# newMain.net
KiCad netlist of a schematic drawn in EAGLE
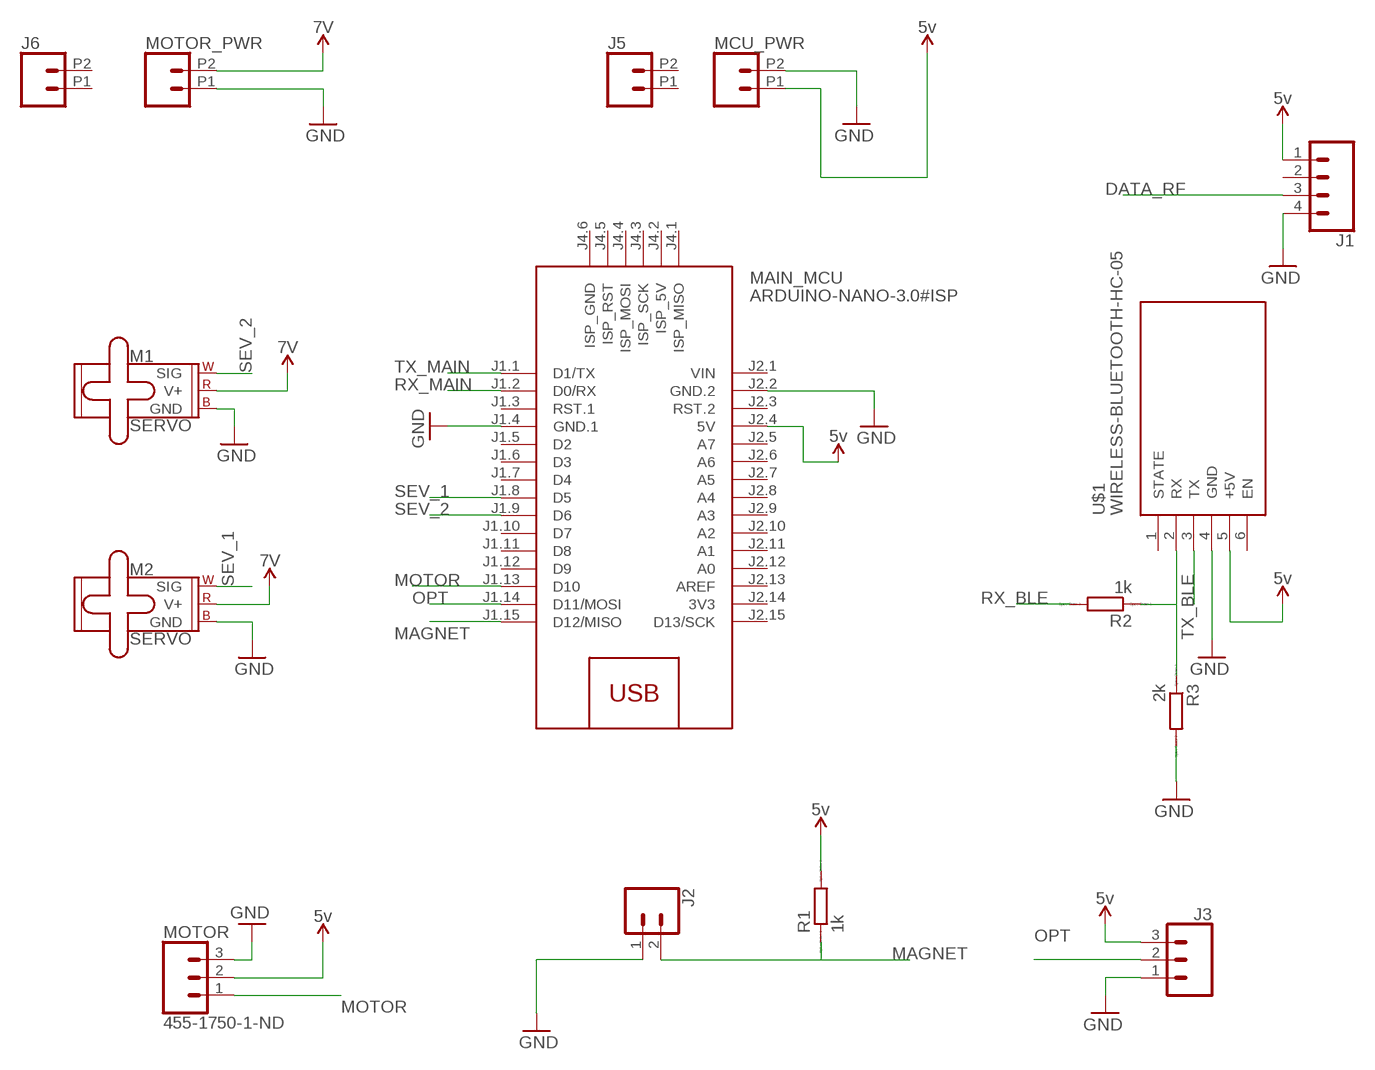
[diagram p0: schematic, sheet 1]

(export (version "E")
  (design (tool "Eeschema 10.0.6"))
  (components
    (comp (ref "J1")
      (value "CONN_04")
      (footprint "eagle-import:1X04")
      (libsource (lib "eagle-import") (part "CONN_04"))
    )
    (comp (ref "J2")
      (value "CONN_02")
      (footprint "eagle-import:1X02")
      (libsource (lib "eagle-import") (part "CONN_02"))
    )
    (comp (ref "J3")
      (value "CONN_03LOCK")
      (footprint "eagle-import:1X03_LOCK")
      (libsource (lib "eagle-import") (part "CONN_03LOCK"))
    )
    (comp (ref "J5")
      (value "CONN_022.54MM_SCREWTERM")
      (footprint "eagle-import:1X02_2.54_SCREWTERM")
      (libsource (lib "eagle-import") (part "SparkFun-Retired_CONN_022.54MM_SCREWTERM"))
    )
    (comp (ref "J6")
      (value "CONN_022.54MM_SCREWTERM")
      (footprint "eagle-import:1X02_2.54_SCREWTERM")
      (libsource (lib "eagle-import") (part "SparkFun-Retired_CONN_022.54MM_SCREWTERM"))
    )
    (comp (ref "M1")
      (value "SERVO")
      (footprint "eagle-import:1X03")
      (libsource (lib "eagle-import") (part "SERVO"))
    )
    (comp (ref "M2")
      (value "SERVO")
      (footprint "eagle-import:1X03")
      (libsource (lib "eagle-import") (part "SERVO"))
    )
    (comp (ref "MAIN_MCU")
      (value "ARDUINO-NANO-3.0#ISP")
      (footprint "eagle-import:ARDUINO-NANO-3.0#ISP")
      (libsource (lib "eagle-import") (part "ARDUINO-NANO-3.0#ISP"))
    )
    (comp (ref "MCU_PWR")
      (value "CONN_022.54MM_SCREWTERM")
      (footprint "eagle-import:1X02_2.54_SCREWTERM")
      (libsource (lib "eagle-import") (part "CONN_022.54MM_SCREWTERM"))
    )
    (comp (ref "MOTOR")
      (value "455-1750-1-ND")
      (footprint "eagle-import:1X03")
      (libsource (lib "eagle-import") (part "CONN_03"))
    )
    (comp (ref "MOTOR_PWR")
      (value "CONN_022.54MM_SCREWTERM")
      (footprint "eagle-import:1X02_2.54_SCREWTERM")
      (libsource (lib "eagle-import") (part "CONN_022.54MM_SCREWTERM"))
    )
    (comp (ref "R1")
      (value "1k")
      (footprint "eagle-import:0207_10")
      (libsource (lib "eagle-import") (part "R0207/10"))
    )
    (comp (ref "R2")
      (value "1k")
      (footprint "eagle-import:0207_10")
      (libsource (lib "eagle-import") (part "R0207/10"))
    )
    (comp (ref "R3")
      (value "2k")
      (footprint "eagle-import:0207_10")
      (libsource (lib "eagle-import") (part "R0207/10"))
    )
    (comp (ref "U$1")
      (value "WIRELESS-BLUETOOTH-HC-05")
      (footprint "eagle-import:WIRELESS-BLUETOOTH-HC-05")
      (libsource (lib "eagle-import") (part "WIRELESS-BLUETOOTH-HC-05"))
    )
  )
  (nets
    (net (code "1") (name "/3V3") (class "Default")
      (node (ref "MAIN_MCU") (pin "J2.14") (pinfunction "3V3_J2.14") (pintype "power_in"))
    )
    (net (code "2") (name "/DATA_RF") (class "Default")
      (node (ref "J1") (pin "3") (pinfunction "3_3") (pintype "passive"))
    )
    (net (code "3") (name "/MAGNET") (class "Default")
      (node (ref "J2") (pin "2") (pinfunction "2_2") (pintype "passive"))
      (node (ref "MAIN_MCU") (pin "J1.15") (pinfunction "D12/MISO_J1.15") (pintype "bidirectional"))
      (node (ref "R1") (pin "1") (pinfunction "1_1") (pintype "passive"))
    )
    (net (code "4") (name "/MOTOR") (class "Default")
      (node (ref "MAIN_MCU") (pin "J1.13") (pinfunction "D10_J1.13") (pintype "bidirectional"))
      (node (ref "MOTOR") (pin "1") (pinfunction "1_1") (pintype "passive"))
    )
    (net (code "5") (name "/OPT") (class "Default")
      (node (ref "J3") (pin "2") (pinfunction "2_2") (pintype "passive"))
      (node (ref "MAIN_MCU") (pin "J1.14") (pinfunction "D11/MOSI_J1.14") (pintype "bidirectional"))
    )
    (net (code "6") (name "/RX_BLE") (class "Default")
      (node (ref "R2") (pin "2") (pinfunction "2_2") (pintype "passive"))
    )
    (net (code "7") (name "/RX_MAIN") (class "Default")
      (node (ref "MAIN_MCU") (pin "J1.2") (pinfunction "D0/RX_J1.2") (pintype "bidirectional"))
    )
    (net (code "8") (name "/SEV_1") (class "Default")
      (node (ref "M2") (pin "1") (pinfunction "SIG_1") (pintype "bidirectional"))
      (node (ref "MAIN_MCU") (pin "J1.8") (pinfunction "D5_J1.8") (pintype "bidirectional"))
    )
    (net (code "9") (name "/SEV_2") (class "Default")
      (node (ref "M1") (pin "1") (pinfunction "SIG_1") (pintype "bidirectional"))
      (node (ref "MAIN_MCU") (pin "J1.9") (pinfunction "D6_J1.9") (pintype "bidirectional"))
    )
    (net (code "10") (name "/TX_BLE") (class "Default")
      (node (ref "U$1") (pin "3") (pinfunction "TX_3") (pintype "bidirectional"))
    )
    (net (code "11") (name "/TX_MAIN") (class "Default")
      (node (ref "MAIN_MCU") (pin "J1.1") (pinfunction "D1/TX_J1.1") (pintype "bidirectional"))
    )
    (net (code "12") (name "/VIN") (class "Default")
      (node (ref "MAIN_MCU") (pin "J2.1") (pinfunction "VIN_J2.1") (pintype "power_in"))
    )
    (net (code "13") (name "5v") (class "Default")
      (node (ref "J1") (pin "1") (pinfunction "1_1") (pintype "passive"))
      (node (ref "J3") (pin "3") (pinfunction "3_3") (pintype "passive"))
      (node (ref "MAIN_MCU") (pin "J2.4") (pinfunction "5V_J2.4") (pintype "power_in"))
      (node (ref "MCU_PWR") (pin "P1") (pinfunction "1_P1") (pintype "passive"))
      (node (ref "MOTOR") (pin "2") (pinfunction "2_2") (pintype "passive"))
      (node (ref "R1") (pin "2") (pinfunction "2_2") (pintype "passive"))
      (node (ref "U$1") (pin "5") (pinfunction "+5V_5") (pintype "power_in"))
    )
    (net (code "14") (name "7V") (class "Default")
      (node (ref "M1") (pin "2") (pinfunction "V+_2") (pintype "bidirectional"))
      (node (ref "M2") (pin "2") (pinfunction "V+_2") (pintype "bidirectional"))
      (node (ref "MOTOR_PWR") (pin "P2") (pinfunction "2_P2") (pintype "passive"))
    )
    (net (code "15") (name "GND") (class "Default")
      (node (ref "J1") (pin "4") (pinfunction "4_4") (pintype "passive"))
      (node (ref "J2") (pin "1") (pinfunction "1_1") (pintype "passive"))
      (node (ref "J3") (pin "1") (pinfunction "1_1") (pintype "passive"))
      (node (ref "M1") (pin "3") (pinfunction "GND_3") (pintype "bidirectional"))
      (node (ref "M2") (pin "3") (pinfunction "GND_3") (pintype "bidirectional"))
      (node (ref "MAIN_MCU") (pin "J1.4") (pinfunction "GND.1_J1.4") (pintype "power_in"))
      (node (ref "MAIN_MCU") (pin "J2.2") (pinfunction "GND.2_J2.2") (pintype "power_in"))
      (node (ref "MCU_PWR") (pin "P2") (pinfunction "2_P2") (pintype "passive"))
      (node (ref "MOTOR") (pin "3") (pinfunction "3_3") (pintype "passive"))
      (node (ref "MOTOR_PWR") (pin "P1") (pinfunction "1_P1") (pintype "passive"))
      (node (ref "R3") (pin "2") (pinfunction "2_2") (pintype "passive"))
      (node (ref "U$1") (pin "4") (pinfunction "GND_4") (pintype "power_in"))
    )
    (net (code "16") (name "Net-(U$1-RX)") (class "Default")
      (node (ref "R2") (pin "1") (pinfunction "1_1") (pintype "passive"))
      (node (ref "R3") (pin "1") (pinfunction "1_1") (pintype "passive"))
      (node (ref "U$1") (pin "2") (pinfunction "RX_2") (pintype "bidirectional"))
    )
    (net (code "17") (name "unconnected-(J1-Pad2)") (class "Default")
      (node (ref "J1") (pin "2") (pinfunction "2_2") (pintype "passive"))
    )
    (net (code "18") (name "unconnected-(J5-1-PadP1)") (class "Default")
      (node (ref "J5") (pin "P1") (pinfunction "1_P1") (pintype "passive"))
    )
    (net (code "19") (name "unconnected-(J5-2-PadP2)") (class "Default")
      (node (ref "J5") (pin "P2") (pinfunction "2_P2") (pintype "passive"))
    )
    (net (code "20") (name "unconnected-(J6-1-PadP1)") (class "Default")
      (node (ref "J6") (pin "P1") (pinfunction "1_P1") (pintype "passive"))
    )
    (net (code "21") (name "unconnected-(J6-2-PadP2)") (class "Default")
      (node (ref "J6") (pin "P2") (pinfunction "2_P2") (pintype "passive"))
    )
    (net (code "22") (name "unconnected-(MAIN_MCU-A0-PadJ2.12)") (class "Default")
      (node (ref "MAIN_MCU") (pin "J2.12") (pinfunction "A0_J2.12") (pintype "bidirectional"))
    )
    (net (code "23") (name "unconnected-(MAIN_MCU-A1-PadJ2.11)") (class "Default")
      (node (ref "MAIN_MCU") (pin "J2.11") (pinfunction "A1_J2.11") (pintype "bidirectional"))
    )
    (net (code "24") (name "unconnected-(MAIN_MCU-A2-PadJ2.10)") (class "Default")
      (node (ref "MAIN_MCU") (pin "J2.10") (pinfunction "A2_J2.10") (pintype "bidirectional"))
    )
    (net (code "25") (name "unconnected-(MAIN_MCU-A3-PadJ2.9)") (class "Default")
      (node (ref "MAIN_MCU") (pin "J2.9") (pinfunction "A3_J2.9") (pintype "bidirectional"))
    )
    (net (code "26") (name "unconnected-(MAIN_MCU-A4-PadJ2.8)") (class "Default")
      (node (ref "MAIN_MCU") (pin "J2.8") (pinfunction "A4_J2.8") (pintype "bidirectional"))
    )
    (net (code "27") (name "unconnected-(MAIN_MCU-A5-PadJ2.7)") (class "Default")
      (node (ref "MAIN_MCU") (pin "J2.7") (pinfunction "A5_J2.7") (pintype "bidirectional"))
    )
    (net (code "28") (name "unconnected-(MAIN_MCU-A6-PadJ2.6)") (class "Default")
      (node (ref "MAIN_MCU") (pin "J2.6") (pinfunction "A6_J2.6") (pintype "bidirectional"))
    )
    (net (code "29") (name "unconnected-(MAIN_MCU-A7-PadJ2.5)") (class "Default")
      (node (ref "MAIN_MCU") (pin "J2.5") (pinfunction "A7_J2.5") (pintype "bidirectional"))
    )
    (net (code "30") (name "unconnected-(MAIN_MCU-AREF-PadJ2.13)") (class "Default")
      (node (ref "MAIN_MCU") (pin "J2.13") (pinfunction "AREF_J2.13") (pintype "bidirectional"))
    )
    (net (code "31") (name "unconnected-(MAIN_MCU-D2-PadJ1.5)") (class "Default")
      (node (ref "MAIN_MCU") (pin "J1.5") (pinfunction "D2_J1.5") (pintype "bidirectional"))
    )
    (net (code "32") (name "unconnected-(MAIN_MCU-D3-PadJ1.6)") (class "Default")
      (node (ref "MAIN_MCU") (pin "J1.6") (pinfunction "D3_J1.6") (pintype "bidirectional"))
    )
    (net (code "33") (name "unconnected-(MAIN_MCU-D4-PadJ1.7)") (class "Default")
      (node (ref "MAIN_MCU") (pin "J1.7") (pinfunction "D4_J1.7") (pintype "bidirectional"))
    )
    (net (code "34") (name "unconnected-(MAIN_MCU-D7-PadJ1.10)") (class "Default")
      (node (ref "MAIN_MCU") (pin "J1.10") (pinfunction "D7_J1.10") (pintype "bidirectional"))
    )
    (net (code "35") (name "unconnected-(MAIN_MCU-D8-PadJ1.11)") (class "Default")
      (node (ref "MAIN_MCU") (pin "J1.11") (pinfunction "D8_J1.11") (pintype "bidirectional"))
    )
    (net (code "36") (name "unconnected-(MAIN_MCU-D9-PadJ1.12)") (class "Default")
      (node (ref "MAIN_MCU") (pin "J1.12") (pinfunction "D9_J1.12") (pintype "bidirectional"))
    )
    (net (code "37") (name "unconnected-(MAIN_MCU-D13{slash}SCK-PadJ2.15)") (class "Default")
      (node (ref "MAIN_MCU") (pin "J2.15") (pinfunction "D13/SCK_J2.15") (pintype "bidirectional"))
    )
    (net (code "38") (name "unconnected-(MAIN_MCU-ISP_5V-PadJ4.2)") (class "Default")
      (node (ref "MAIN_MCU") (pin "J4.2") (pinfunction "ISP_5V_J4.2") (pintype "bidirectional"))
    )
    (net (code "39") (name "unconnected-(MAIN_MCU-ISP_GND-PadJ4.6)") (class "Default")
      (node (ref "MAIN_MCU") (pin "J4.6") (pinfunction "ISP_GND_J4.6") (pintype "bidirectional"))
    )
    (net (code "40") (name "unconnected-(MAIN_MCU-ISP_MISO-PadJ4.1)") (class "Default")
      (node (ref "MAIN_MCU") (pin "J4.1") (pinfunction "ISP_MISO_J4.1") (pintype "bidirectional"))
    )
    (net (code "41") (name "unconnected-(MAIN_MCU-ISP_MOSI-PadJ4.4)") (class "Default")
      (node (ref "MAIN_MCU") (pin "J4.4") (pinfunction "ISP_MOSI_J4.4") (pintype "bidirectional"))
    )
    (net (code "42") (name "unconnected-(MAIN_MCU-ISP_RST-PadJ4.5)") (class "Default")
      (node (ref "MAIN_MCU") (pin "J4.5") (pinfunction "ISP_RST_J4.5") (pintype "bidirectional"))
    )
    (net (code "43") (name "unconnected-(MAIN_MCU-ISP_SCK-PadJ4.3)") (class "Default")
      (node (ref "MAIN_MCU") (pin "J4.3") (pinfunction "ISP_SCK_J4.3") (pintype "bidirectional"))
    )
    (net (code "44") (name "unconnected-(MAIN_MCU-RST.1-PadJ1.3)") (class "Default")
      (node (ref "MAIN_MCU") (pin "J1.3") (pinfunction "RST.1_J1.3") (pintype "bidirectional"))
    )
    (net (code "45") (name "unconnected-(MAIN_MCU-RST.2-PadJ2.3)") (class "Default")
      (node (ref "MAIN_MCU") (pin "J2.3") (pinfunction "RST.2_J2.3") (pintype "bidirectional"))
    )
    (net (code "46") (name "unconnected-(U$1-EN-Pad6)") (class "Default")
      (node (ref "U$1") (pin "6") (pinfunction "EN_6") (pintype "bidirectional"))
    )
    (net (code "47") (name "unconnected-(U$1-STATE-Pad1)") (class "Default")
      (node (ref "U$1") (pin "1") (pinfunction "STATE_1") (pintype "bidirectional"))
    )
  )
)
